# ProPrj_AD835__2025-07-16.net
KiCad netlist of a schematic drawn in EasyEDA Pro
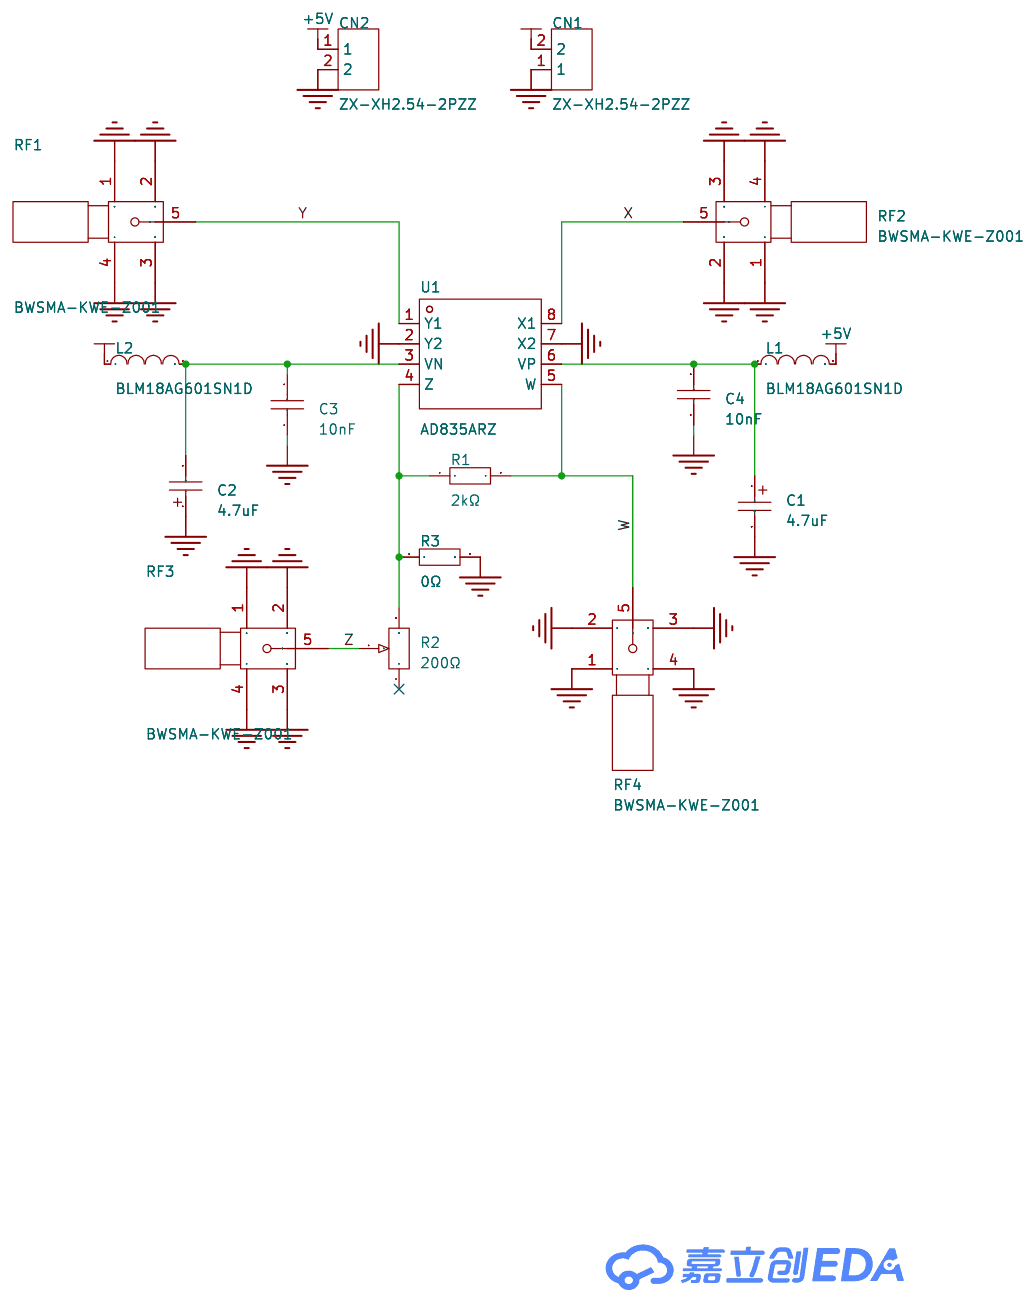
[diagram p0: schematic sheet]

(export (version "E")
  (design (tool "Eeschema 10.0.6"))
  (components
    (comp (ref "C1")
      (value "4.7uF")
      (footprint "easyedapro:CASE-A_3216")
      (description "容值:4.7uF;精度:±10%;额定电压:16V;等效串联电阻:4Ω@100kHz;")
      (fields (field (name "Manufacturer Part") "TAJA475K016RNJ") (field (name "Manufacturer") "Kyocera AVX"))
      (libsource (lib "easyedapro") (part "TAJA475K016RNJ"))
    )
    (comp (ref "C2")
      (value "4.7uF")
      (footprint "easyedapro:CASE-A_3216")
      (description "容值:4.7uF;精度:±10%;额定电压:16V;等效串联电阻:4Ω@100kHz;")
      (fields (field (name "Manufacturer Part") "TAJA475K016RNJ") (field (name "Manufacturer") "Kyocera AVX"))
      (libsource (lib "easyedapro") (part "TAJA475K016RNJ"))
    )
    (comp (ref "C3")
      (value "10nF")
      (footprint "easyedapro:C0603")
      (description "容值:10nF;精度:±10%;额定电压:50V;温度系数:X7R;")
      (fields (field (name "Manufacturer Part") "0603B103K500NT") (field (name "Manufacturer") "FH(风华)"))
      (libsource (lib "easyedapro") (part "0603B103K500NT"))
    )
    (comp (ref "C4")
      (value "10nF")
      (footprint "easyedapro:C0603")
      (description "容值:10nF;精度:±10%;额定电压:50V;温度系数:X7R;")
      (fields (field (name "Manufacturer Part") "0603B103K500NT") (field (name "Manufacturer") "FH(风华)"))
      (libsource (lib "easyedapro") (part "0603B103K500NT"))
    )
    (comp (ref "CN1")
      (value "ZX-XH2.54-2PZZ")
      (footprint "easyedapro:CONN-TH_2P-P2.50_HX25003-2A")
      (fields (field (name "Manufacturer") "Megastar(兆星)"))
      (libsource (lib "easyedapro") (part "ZX-XH2.54-2PZZ"))
    )
    (comp (ref "CN2")
      (value "ZX-XH2.54-2PZZ")
      (footprint "easyedapro:CONN-TH_2P-P2.50_HX25003-2A")
      (fields (field (name "Manufacturer") "Megastar(兆星)"))
      (libsource (lib "easyedapro") (part "ZX-XH2.54-2PZZ"))
    )
    (comp (ref "L1")
      (value "BLM18AG601SN1D")
      (footprint "easyedapro:L0603")
      (description "阻抗@频率:600Ω@100MHz;误差:±25%;直流电阻(DCR):380mΩ;")
      (fields (field (name "Manufacturer") "muRata(村田)"))
      (libsource (lib "easyedapro") (part "BLM18AG601SN1D"))
    )
    (comp (ref "L2")
      (value "BLM18AG601SN1D")
      (footprint "easyedapro:L0603")
      (description "阻抗@频率:600Ω@100MHz;误差:±25%;直流电阻(DCR):380mΩ;")
      (fields (field (name "Manufacturer") "muRata(村田)"))
      (libsource (lib "easyedapro") (part "BLM18AG601SN1D"))
    )
    (comp (ref "R1")
      (value "2kΩ")
      (footprint "easyedapro:R0603")
      (description "电阻类型:厚膜电阻;阻值:2kΩ;精度:±1%;功率:100mW;最大工作电压:75V;温度系数:±100ppm/°C;")
      (fields
        (field (name "Manufacturer Part") "0603WAF2001T5E")
        (field (name "Manufacturer") "UNI-ROYAL(厚声)")
      )
      (libsource (lib "easyedapro") (part "0603WAF2001T5E"))
    )
    (comp (ref "R2")
      (value "200Ω")
      (footprint "easyedapro:RES-ADJ-TH_3P-L9.5-W4.9-P2.50-L_3296W")
      (description "阻值:200Ω;精度:±10%;")
      (fields (field (name "Manufacturer Part") "3296W-1-201") (field (name "Manufacturer") "BOCHEN(博晨)"))
      (libsource (lib "easyedapro") (part "3296W-1-201"))
    )
    (comp (ref "R3")
      (value "0Ω")
      (footprint "easyedapro:R0603")
      (description "电阻类型:厚膜电阻;阻值:0Ω;精度:±1%;功率:100mW;最大工作电压:75V;")
      (fields
        (field (name "Manufacturer Part") "0603WAF0000T5E")
        (field (name "Manufacturer") "UNI-ROYAL(厚声)")
      )
      (libsource (lib "easyedapro") (part "0603WAF0000T5E"))
    )
    (comp (ref "RF1")
      (value "BWSMA-KWE-Z001")
      (footprint "easyedapro:SMA-TH_BWSMA-KWE-Z001")
      (fields (field (name "Manufacturer") "BAT WIRELESS(蝙蝠无线)"))
      (libsource (lib "easyedapro") (part "BWSMA-KWE-Z001"))
    )
    (comp (ref "RF2")
      (value "BWSMA-KWE-Z001")
      (footprint "easyedapro:SMA-TH_BWSMA-KWE-Z001")
      (fields (field (name "Manufacturer") "BAT WIRELESS(蝙蝠无线)"))
      (libsource (lib "easyedapro") (part "BWSMA-KWE-Z001"))
    )
    (comp (ref "RF3")
      (value "BWSMA-KWE-Z001")
      (footprint "easyedapro:SMA-TH_BWSMA-KWE-Z001")
      (fields (field (name "Manufacturer") "BAT WIRELESS(蝙蝠无线)"))
      (libsource (lib "easyedapro") (part "BWSMA-KWE-Z001"))
    )
    (comp (ref "RF4")
      (value "BWSMA-KWE-Z001")
      (footprint "easyedapro:SMA-TH_BWSMA-KWE-Z001")
      (fields (field (name "Manufacturer") "BAT WIRELESS(蝙蝠无线)"))
      (libsource (lib "easyedapro") (part "BWSMA-KWE-Z001"))
    )
    (comp (ref "U1")
      (value "AD835ARZ")
      (footprint "easyedapro:SOIC-8_L4.9-W3.9-P1.27-LS6.0-TL")
      (description "象限:四象限;压摆率(SR):1000V/us;带宽:250MHz;")
      (fields (field (name "Manufacturer") "ADI(亚德诺)"))
      (libsource (lib "easyedapro") (part "AD835ARZ"))
    )
  )
  (nets
    (net (code "1") (name "+5V") (class "Default")
      (node (ref "CN2") (pin "1") (pinfunction "1_1") (pintype "unspecified"))
      (node (ref "L1") (pin "2") (pinfunction "2_2") (pintype "unspecified"))
    )
    (net (code "2") (name "-5V") (class "Default")
      (node (ref "CN1") (pin "2") (pinfunction "2_2") (pintype "unspecified"))
      (node (ref "L2") (pin "1") (pinfunction "1_1") (pintype "unspecified"))
    )
    (net (code "3") (name "/W") (class "Default")
      (node (ref "R1") (pin "2") (pinfunction "2_2") (pintype "input"))
      (node (ref "RF4") (pin "5") (pinfunction "5_5") (pintype "unspecified"))
      (node (ref "U1") (pin "5") (pinfunction "W_5") (pintype "unspecified"))
    )
    (net (code "4") (name "/X") (class "Default")
      (node (ref "RF2") (pin "5") (pinfunction "5_5") (pintype "unspecified"))
      (node (ref "U1") (pin "8") (pinfunction "X1_8") (pintype "unspecified"))
    )
    (net (code "5") (name "/Y") (class "Default")
      (node (ref "RF1") (pin "5") (pinfunction "5_5") (pintype "unspecified"))
      (node (ref "U1") (pin "1") (pinfunction "Y1_1") (pintype "unspecified"))
    )
    (net (code "6") (name "/Z") (class "Default")
      (node (ref "R2") (pin "2") (pinfunction "2_2") (pintype "input"))
      (node (ref "RF3") (pin "5") (pinfunction "5_5") (pintype "unspecified"))
    )
    (net (code "7") (name "GND") (class "Default")
      (node (ref "C1") (pin "2") (pinfunction "2_2") (pintype "input"))
      (node (ref "C2") (pin "1") (pinfunction "1_1") (pintype "input"))
      (node (ref "C3") (pin "1") (pinfunction "1_1") (pintype "input"))
      (node (ref "C4") (pin "1") (pinfunction "1_1") (pintype "input"))
      (node (ref "CN1") (pin "1") (pinfunction "1_1") (pintype "unspecified"))
      (node (ref "CN2") (pin "2") (pinfunction "2_2") (pintype "unspecified"))
      (node (ref "R3") (pin "2") (pinfunction "2_2") (pintype "input"))
      (node (ref "RF1") (pin "1") (pinfunction "1_1") (pintype "unspecified"))
      (node (ref "RF1") (pin "2") (pinfunction "2_2") (pintype "unspecified"))
      (node (ref "RF1") (pin "3") (pinfunction "3_3") (pintype "unspecified"))
      (node (ref "RF1") (pin "4") (pinfunction "4_4") (pintype "unspecified"))
      (node (ref "RF2") (pin "1") (pinfunction "1_1") (pintype "unspecified"))
      (node (ref "RF2") (pin "2") (pinfunction "2_2") (pintype "unspecified"))
      (node (ref "RF2") (pin "3") (pinfunction "3_3") (pintype "unspecified"))
      (node (ref "RF2") (pin "4") (pinfunction "4_4") (pintype "unspecified"))
      (node (ref "RF3") (pin "1") (pinfunction "1_1") (pintype "unspecified"))
      (node (ref "RF3") (pin "2") (pinfunction "2_2") (pintype "unspecified"))
      (node (ref "RF3") (pin "3") (pinfunction "3_3") (pintype "unspecified"))
      (node (ref "RF3") (pin "4") (pinfunction "4_4") (pintype "unspecified"))
      (node (ref "RF4") (pin "1") (pinfunction "1_1") (pintype "unspecified"))
      (node (ref "RF4") (pin "2") (pinfunction "2_2") (pintype "unspecified"))
      (node (ref "RF4") (pin "3") (pinfunction "3_3") (pintype "unspecified"))
      (node (ref "RF4") (pin "4") (pinfunction "4_4") (pintype "unspecified"))
      (node (ref "U1") (pin "2") (pinfunction "Y2_2") (pintype "unspecified"))
      (node (ref "U1") (pin "7") (pinfunction "X2_7") (pintype "unspecified"))
    )
    (net (code "8") (name "Net-(U1-VN)") (class "Default")
      (node (ref "C2") (pin "2") (pinfunction "2_2") (pintype "input"))
      (node (ref "C3") (pin "2") (pinfunction "2_2") (pintype "input"))
      (node (ref "L2") (pin "2") (pinfunction "2_2") (pintype "unspecified"))
      (node (ref "U1") (pin "3") (pinfunction "VN_3") (pintype "unspecified"))
    )
    (net (code "9") (name "Net-(U1-VP)") (class "Default")
      (node (ref "C1") (pin "1") (pinfunction "1_1") (pintype "input"))
      (node (ref "C4") (pin "2") (pinfunction "2_2") (pintype "input"))
      (node (ref "L1") (pin "1") (pinfunction "1_1") (pintype "unspecified"))
      (node (ref "U1") (pin "6") (pinfunction "VP_6") (pintype "unspecified"))
    )
    (net (code "10") (name "Net-(U1-Z)") (class "Default")
      (node (ref "R1") (pin "1") (pinfunction "1_1") (pintype "input"))
      (node (ref "R2") (pin "3") (pinfunction "3_3") (pintype "input"))
      (node (ref "R3") (pin "1") (pinfunction "1_1") (pintype "input"))
      (node (ref "U1") (pin "4") (pinfunction "Z_4") (pintype "unspecified"))
    )
    (net (code "11") (name "unconnected-(R2-Pad1)") (class "Default")
      (node (ref "R2") (pin "1") (pinfunction "1_1") (pintype "input+no_connect"))
    )
  )
)
